# MCU_Standard.net
KiCad netlist of a schematic drawn in EAGLE
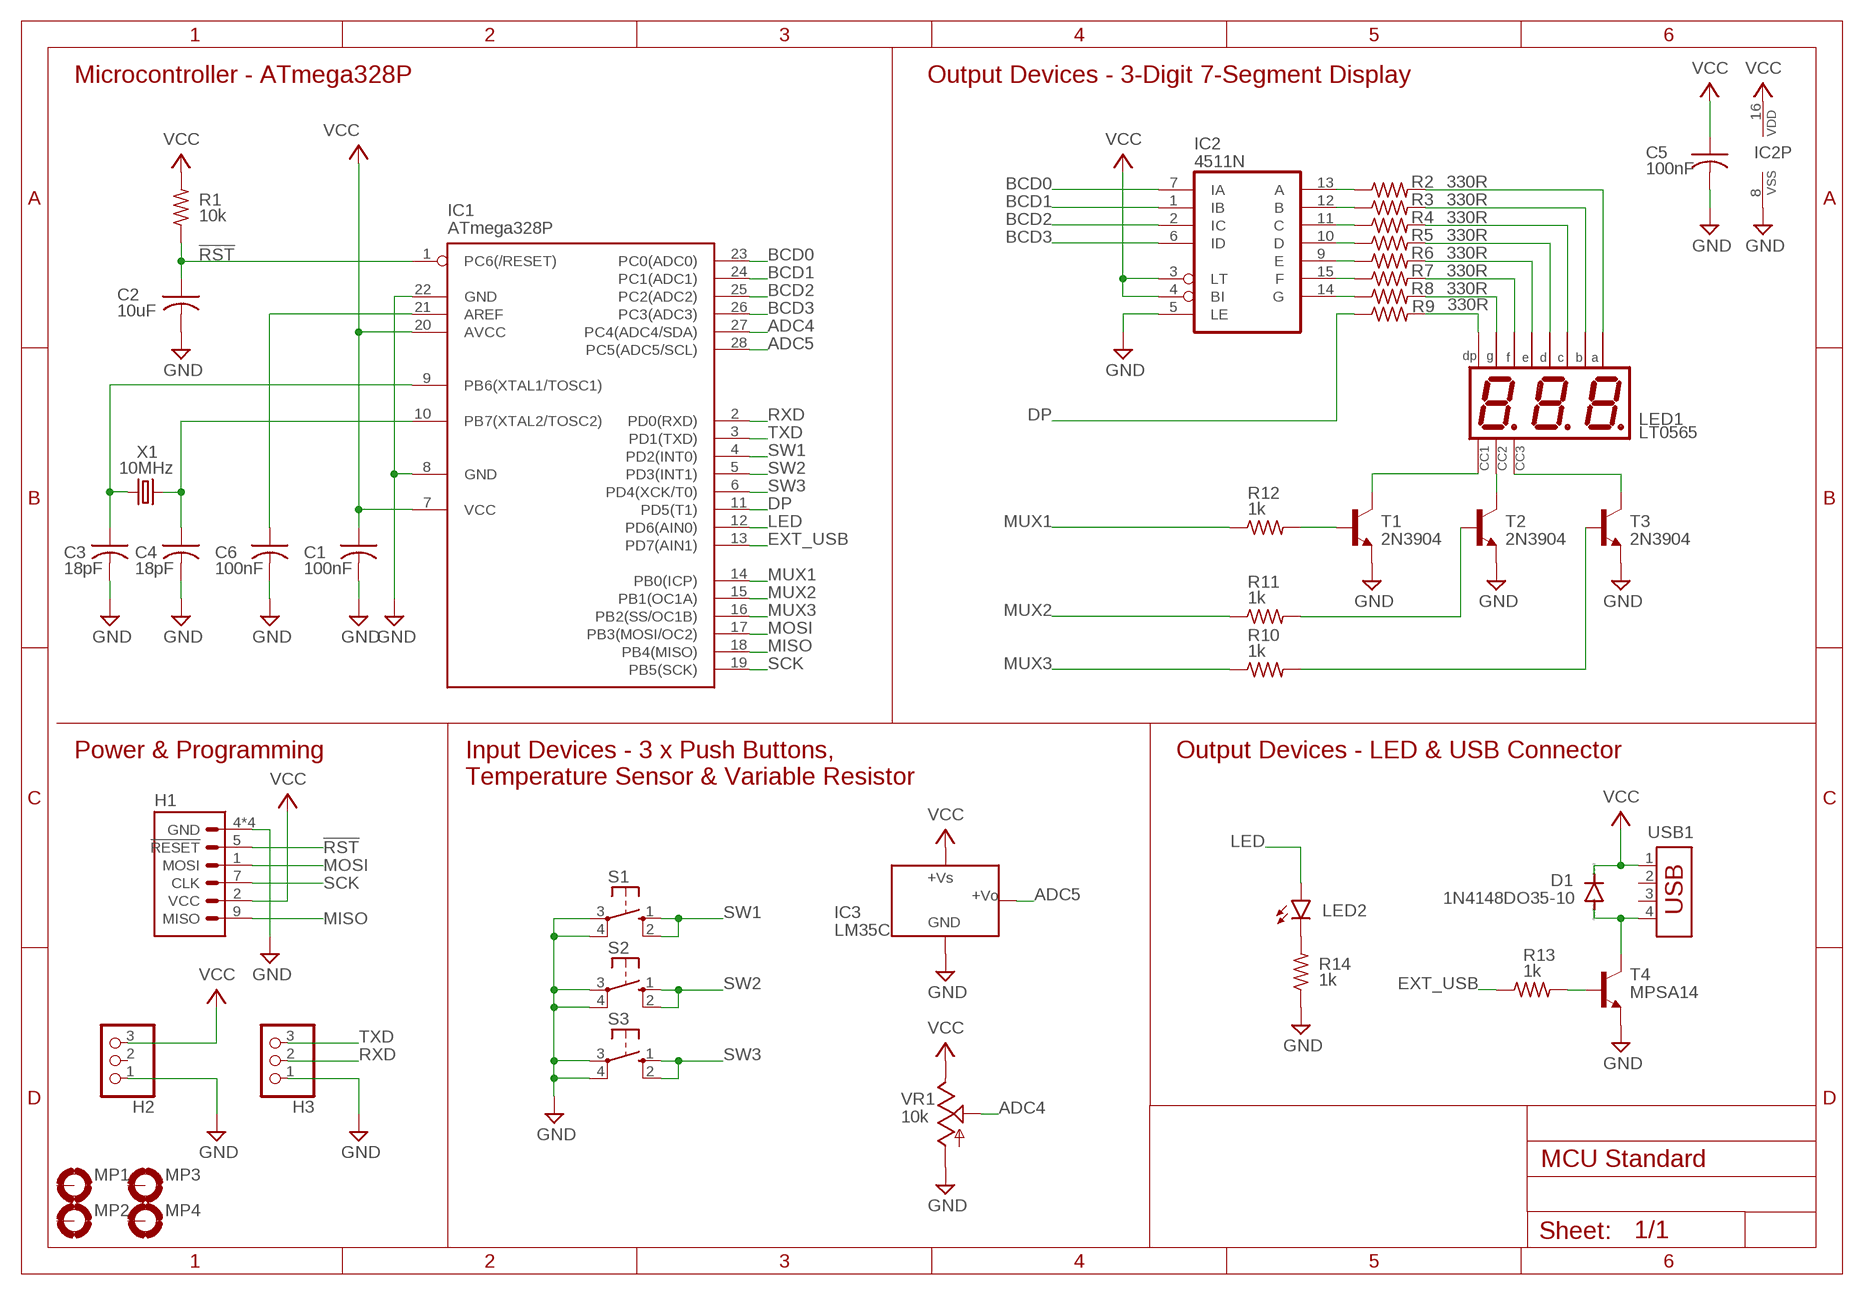
[diagram p0: schematic, sheet 1]

(export (version "E")
  (design (tool "Eeschema 10.0.6"))
  (components
    (comp (ref "C1")
      (value "100nF")
      (footprint "eagle-import:C050-024X044")
      (libsource (lib "eagle-import") (part "C-US050-024X044"))
    )
    (comp (ref "C2")
      (value "10uF")
      (footprint "eagle-import:C050-024X044")
      (libsource (lib "eagle-import") (part "C-US050-024X044"))
    )
    (comp (ref "C3")
      (value "18pF")
      (footprint "eagle-import:C050-024X044")
      (libsource (lib "eagle-import") (part "C-US050-024X044"))
    )
    (comp (ref "C4")
      (value "18pF")
      (footprint "eagle-import:C050-024X044")
      (libsource (lib "eagle-import") (part "C-US050-024X044"))
    )
    (comp (ref "C5")
      (value "100nF")
      (footprint "eagle-import:C050-024X044")
      (libsource (lib "eagle-import") (part "C-US050-024X044"))
    )
    (comp (ref "C6")
      (value "100nF")
      (footprint "eagle-import:C050-024X044")
      (libsource (lib "eagle-import") (part "C-US050-024X044"))
    )
    (comp (ref "D1")
      (value "1N4148DO35-10")
      (footprint "eagle-import:DO35-10")
      (libsource (lib "eagle-import") (part "1N4148DO35-10"))
    )
    (comp (ref "H1")
      (value "MISO_MOSI_IPC-10V")
      (footprint "eagle-import:IDC-10V")
      (libsource (lib "eagle-import") (part "MISO_MOSI_IPC-10V"))
    )
    (comp (ref "H2")
      (value "PINHD-1X03_2.54-90°")
      (footprint "eagle-import:1X03_90")
      (libsource (lib "eagle-import") (part "PINHD-1X03_2.54-90°"))
    )
    (comp (ref "H3")
      (value "PINHD-1X03_2.54-90°")
      (footprint "eagle-import:1X03_90")
      (libsource (lib "eagle-import") (part "PINHD-1X03_2.54-90°"))
    )
    (comp (ref "IC1")
      (value "ATmega328P")
      (footprint "eagle-import:DIL28-3")
      (libsource (lib "eagle-import") (part "MEGA8-P"))
    )
    (comp (ref "IC2")
      (value "4511N")
      (footprint "eagle-import:DIL16")
      (libsource (lib "eagle-import") (part "4511N"))
    )
    (comp (ref "IC3")
      (value "LM35C")
      (footprint "eagle-import:TO92")
      (libsource (lib "eagle-import") (part "LM35C"))
    )
    (comp (ref "LED1")
      (value "LT0565")
      (footprint "eagle-import:BX56_BX55")
      (libsource (lib "eagle-import") (part "LT0565"))
    )
    (comp (ref "LED2")
      (value "LED3MM")
      (footprint "eagle-import:LED3MM")
      (libsource (lib "eagle-import") (part "LED3MM"))
    )
    (comp (ref "MP1")
      (value "MOUNT-PAD-ROUND3.2")
      (footprint "eagle-import:3,2-PAD")
      (libsource (lib "eagle-import") (part "MOUNT-PAD-ROUND3.2"))
    )
    (comp (ref "MP2")
      (value "MOUNT-PAD-ROUND3.2")
      (footprint "eagle-import:3,2-PAD")
      (libsource (lib "eagle-import") (part "MOUNT-PAD-ROUND3.2"))
    )
    (comp (ref "MP3")
      (value "MOUNT-PAD-ROUND3.2")
      (footprint "eagle-import:3,2-PAD")
      (libsource (lib "eagle-import") (part "MOUNT-PAD-ROUND3.2"))
    )
    (comp (ref "MP4")
      (value "MOUNT-PAD-ROUND3.2")
      (footprint "eagle-import:3,2-PAD")
      (libsource (lib "eagle-import") (part "MOUNT-PAD-ROUND3.2"))
    )
    (comp (ref "R1")
      (value "10k")
      (footprint "eagle-import:0207_10")
      (libsource (lib "eagle-import") (part "R-US_0207/10"))
    )
    (comp (ref "R2")
      (value "330R")
      (footprint "eagle-import:0207_10")
      (libsource (lib "eagle-import") (part "R-US_0207/10"))
    )
    (comp (ref "R3")
      (value "330R")
      (footprint "eagle-import:0207_10")
      (libsource (lib "eagle-import") (part "R-US_0207/10"))
    )
    (comp (ref "R4")
      (value "330R")
      (footprint "eagle-import:0207_10")
      (libsource (lib "eagle-import") (part "R-US_0207/10"))
    )
    (comp (ref "R5")
      (value "330R")
      (footprint "eagle-import:0207_10")
      (libsource (lib "eagle-import") (part "R-US_0207/10"))
    )
    (comp (ref "R6")
      (value "330R")
      (footprint "eagle-import:0207_10")
      (libsource (lib "eagle-import") (part "R-US_0207/10"))
    )
    (comp (ref "R7")
      (value "330R")
      (footprint "eagle-import:0207_10")
      (libsource (lib "eagle-import") (part "R-US_0207/10"))
    )
    (comp (ref "R8")
      (value "330R")
      (footprint "eagle-import:0207_10")
      (libsource (lib "eagle-import") (part "R-US_0207/10"))
    )
    (comp (ref "R9")
      (value "330R")
      (footprint "eagle-import:0207_10")
      (libsource (lib "eagle-import") (part "R-US_0207/10"))
    )
    (comp (ref "R10")
      (value "1k")
      (footprint "eagle-import:0207_10")
      (libsource (lib "eagle-import") (part "R-US_0207/10"))
    )
    (comp (ref "R11")
      (value "1k")
      (footprint "eagle-import:0207_10")
      (libsource (lib "eagle-import") (part "R-US_0207/10"))
    )
    (comp (ref "R12")
      (value "1k")
      (footprint "eagle-import:0207_10")
      (libsource (lib "eagle-import") (part "R-US_0207/10"))
    )
    (comp (ref "R13")
      (value "1k")
      (footprint "eagle-import:0207_10")
      (libsource (lib "eagle-import") (part "R-US_0207/10"))
    )
    (comp (ref "R14")
      (value "1k")
      (footprint "eagle-import:0207_10")
      (libsource (lib "eagle-import") (part "R-US_0207/10"))
    )
    (comp (ref "S1")
      (value "10-XX")
      (footprint "eagle-import:B3F-10XX")
      (fields (field (name "MPN") "B3F-1000"))
      (libsource (lib "eagle-import") (part "10-XX"))
    )
    (comp (ref "S2")
      (value "10-XX")
      (footprint "eagle-import:B3F-10XX")
      (fields (field (name "MPN") "B3F-1000"))
      (libsource (lib "eagle-import") (part "10-XX"))
    )
    (comp (ref "S3")
      (value "10-XX")
      (footprint "eagle-import:B3F-10XX")
      (fields (field (name "MPN") "B3F-1000"))
      (libsource (lib "eagle-import") (part "10-XX"))
    )
    (comp (ref "T1")
      (value "2N3904")
      (footprint "eagle-import:TO92")
      (libsource (lib "eagle-import") (part "2N3904"))
    )
    (comp (ref "T2")
      (value "2N3904")
      (footprint "eagle-import:TO92")
      (libsource (lib "eagle-import") (part "2N3904"))
    )
    (comp (ref "T3")
      (value "2N3904")
      (footprint "eagle-import:TO92")
      (libsource (lib "eagle-import") (part "2N3904"))
    )
    (comp (ref "T4")
      (value "MPSA14")
      (footprint "eagle-import:TO92")
      (libsource (lib "eagle-import") (part "MPSA14"))
    )
    (comp (ref "USB1")
      (value "USB-787616")
      (footprint "eagle-import:USB")
      (libsource (lib "eagle-import") (part "USB-787616"))
    )
    (comp (ref "VR1")
      (value "10k")
      (footprint "eagle-import:PT-10")
      (libsource (lib "eagle-import") (part "POTENTIOMETER_PT10"))
    )
    (comp (ref "X1")
      (value "10MHz")
      (footprint "eagle-import:HC49_S")
      (libsource (lib "eagle-import") (part "CRYSTAL_HC49/S"))
    )
  )
  (nets
    (net (code "1") (name "/ADC4") (class "Default")
      (node (ref "IC1") (pin "27") (pinfunction "PC4(ADC4/SDA)_27") (pintype "bidirectional"))
      (node (ref "VR1") (pin "3") (pinfunction "S_3") (pintype "passive"))
    )
    (net (code "2") (name "/ADC5") (class "Default")
      (node (ref "IC1") (pin "28") (pinfunction "PC5(ADC5/SCL)_28") (pintype "bidirectional"))
      (node (ref "IC3") (pin "2") (pinfunction "VO_2") (pintype "output"))
    )
    (net (code "3") (name "/BCD0") (class "Default")
      (node (ref "IC1") (pin "23") (pinfunction "PC0(ADC0)_23") (pintype "bidirectional"))
      (node (ref "IC2") (pin "7") (pinfunction "IA_7") (pintype "input"))
    )
    (net (code "4") (name "/BCD1") (class "Default")
      (node (ref "IC1") (pin "24") (pinfunction "PC1(ADC1)_24") (pintype "bidirectional"))
      (node (ref "IC2") (pin "1") (pinfunction "IB_1") (pintype "input"))
    )
    (net (code "5") (name "/BCD2") (class "Default")
      (node (ref "IC1") (pin "25") (pinfunction "PC2(ADC2)_25") (pintype "bidirectional"))
      (node (ref "IC2") (pin "2") (pinfunction "IC_2") (pintype "input"))
    )
    (net (code "6") (name "/BCD3") (class "Default")
      (node (ref "IC1") (pin "26") (pinfunction "PC3(ADC3)_26") (pintype "bidirectional"))
      (node (ref "IC2") (pin "6") (pinfunction "ID_6") (pintype "input"))
    )
    (net (code "7") (name "/DP") (class "Default")
      (node (ref "IC1") (pin "11") (pinfunction "PD5(T1)_11") (pintype "bidirectional"))
      (node (ref "R9") (pin "1") (pinfunction "1_1") (pintype "passive"))
    )
    (net (code "8") (name "/EXT_USB") (class "Default")
      (node (ref "IC1") (pin "13") (pinfunction "PD7(AIN1)_13") (pintype "bidirectional"))
      (node (ref "R13") (pin "1") (pinfunction "1_1") (pintype "passive"))
    )
    (net (code "9") (name "/LED") (class "Default")
      (node (ref "IC1") (pin "12") (pinfunction "PD6(AIN0)_12") (pintype "bidirectional"))
      (node (ref "LED2") (pin "A") (pinfunction "A_A") (pintype "passive"))
    )
    (net (code "10") (name "/MISO") (class "Default")
      (node (ref "H1") (pin "9") (pinfunction "MISO_9") (pintype "passive"))
      (node (ref "IC1") (pin "18") (pinfunction "PB4(MISO)_18") (pintype "bidirectional"))
    )
    (net (code "11") (name "/MOSI") (class "Default")
      (node (ref "H1") (pin "1") (pinfunction "MOSI_1") (pintype "passive"))
      (node (ref "IC1") (pin "17") (pinfunction "PB3(MOSI/OC2)_17") (pintype "bidirectional"))
    )
    (net (code "12") (name "/MUX1") (class "Default")
      (node (ref "IC1") (pin "14") (pinfunction "PB0(ICP)_14") (pintype "bidirectional"))
      (node (ref "R12") (pin "1") (pinfunction "1_1") (pintype "passive"))
    )
    (net (code "13") (name "/MUX2") (class "Default")
      (node (ref "IC1") (pin "15") (pinfunction "PB1(OC1A)_15") (pintype "bidirectional"))
      (node (ref "R11") (pin "1") (pinfunction "1_1") (pintype "passive"))
    )
    (net (code "14") (name "/MUX3") (class "Default")
      (node (ref "IC1") (pin "16") (pinfunction "PB2(SS/OC1B)_16") (pintype "bidirectional"))
      (node (ref "R10") (pin "1") (pinfunction "1_1") (pintype "passive"))
    )
    (net (code "15") (name "/RXD") (class "Default")
      (node (ref "H3") (pin "2") (pinfunction "2_2") (pintype "passive"))
      (node (ref "IC1") (pin "2") (pinfunction "PD0(RXD)_2") (pintype "bidirectional"))
    )
    (net (code "16") (name "/SCK") (class "Default")
      (node (ref "H1") (pin "7") (pinfunction "CLK_7") (pintype "passive"))
      (node (ref "IC1") (pin "19") (pinfunction "PB5(SCK)_19") (pintype "bidirectional"))
    )
    (net (code "17") (name "/SW1") (class "Default")
      (node (ref "IC1") (pin "4") (pinfunction "PD2(INT0)_4") (pintype "bidirectional"))
      (node (ref "S1") (pin "1") (pinfunction "S_1") (pintype "passive"))
      (node (ref "S1") (pin "2") (pinfunction "S1_2") (pintype "passive"))
    )
    (net (code "18") (name "/SW2") (class "Default")
      (node (ref "IC1") (pin "5") (pinfunction "PD3(INT1)_5") (pintype "bidirectional"))
      (node (ref "S2") (pin "1") (pinfunction "S_1") (pintype "passive"))
      (node (ref "S2") (pin "2") (pinfunction "S1_2") (pintype "passive"))
    )
    (net (code "19") (name "/SW3") (class "Default")
      (node (ref "IC1") (pin "6") (pinfunction "PD4(XCK/T0)_6") (pintype "bidirectional"))
      (node (ref "S3") (pin "1") (pinfunction "S_1") (pintype "passive"))
      (node (ref "S3") (pin "2") (pinfunction "S1_2") (pintype "passive"))
    )
    (net (code "20") (name "/TXD") (class "Default")
      (node (ref "H3") (pin "3") (pinfunction "3_3") (pintype "passive"))
      (node (ref "IC1") (pin "3") (pinfunction "PD1(TXD)_3") (pintype "bidirectional"))
    )
    (net (code "21") (name "/~{RST}") (class "Default")
      (node (ref "C2") (pin "1") (pinfunction "1_1") (pintype "passive"))
      (node (ref "H1") (pin "5") (pinfunction "~{RESET}_5") (pintype "passive"))
      (node (ref "IC1") (pin "1") (pinfunction "PC6(/RESET)_1") (pintype "bidirectional"))
      (node (ref "R1") (pin "1") (pinfunction "1_1") (pintype "passive"))
    )
    (net (code "22") (name "GND") (class "Default")
      (node (ref "C1") (pin "2") (pinfunction "2_2") (pintype "passive"))
      (node (ref "C2") (pin "2") (pinfunction "2_2") (pintype "passive"))
      (node (ref "C3") (pin "2") (pinfunction "2_2") (pintype "passive"))
      (node (ref "C4") (pin "2") (pinfunction "2_2") (pintype "passive"))
      (node (ref "C5") (pin "2") (pinfunction "2_2") (pintype "passive"))
      (node (ref "C6") (pin "2") (pinfunction "2_2") (pintype "passive"))
      (node (ref "H1") (pin "10") (pinfunction "GND_10") (pintype "power_in"))
      (node (ref "H1") (pin "4") (pinfunction "GND_4") (pintype "power_in"))
      (node (ref "H1") (pin "6") (pinfunction "GND_6") (pintype "power_in"))
      (node (ref "H1") (pin "8") (pinfunction "GND_8") (pintype "power_in"))
      (node (ref "H2") (pin "1") (pinfunction "1_1") (pintype "passive"))
      (node (ref "H3") (pin "1") (pinfunction "1_1") (pintype "passive"))
      (node (ref "IC1") (pin "22") (pinfunction "GND_22") (pintype "power_in"))
      (node (ref "IC1") (pin "8") (pinfunction "GND_8") (pintype "power_in"))
      (node (ref "IC2") (pin "5") (pinfunction "LE_5") (pintype "input"))
      (node (ref "IC2") (pin "8") (pinfunction "VSS_8") (pintype "power_in"))
      (node (ref "IC3") (pin "1") (pinfunction "GND_1") (pintype "power_in"))
      (node (ref "R14") (pin "1") (pinfunction "1_1") (pintype "passive"))
      (node (ref "S1") (pin "3") (pinfunction "P_3") (pintype "passive"))
      (node (ref "S1") (pin "4") (pinfunction "P1_4") (pintype "passive"))
      (node (ref "S2") (pin "3") (pinfunction "P_3") (pintype "passive"))
      (node (ref "S2") (pin "4") (pinfunction "P1_4") (pintype "passive"))
      (node (ref "S3") (pin "3") (pinfunction "P_3") (pintype "passive"))
      (node (ref "S3") (pin "4") (pinfunction "P1_4") (pintype "passive"))
      (node (ref "T1") (pin "3") (pinfunction "E_3") (pintype "passive"))
      (node (ref "T2") (pin "3") (pinfunction "E_3") (pintype "passive"))
      (node (ref "T3") (pin "3") (pinfunction "E_3") (pintype "passive"))
      (node (ref "T4") (pin "3") (pinfunction "E_3") (pintype "passive"))
      (node (ref "VR1") (pin "1") (pinfunction "A_1") (pintype "passive"))
    )
    (net (code "23") (name "Net-(IC1-AREF)") (class "Default")
      (node (ref "C6") (pin "1") (pinfunction "1_1") (pintype "passive"))
      (node (ref "IC1") (pin "21") (pinfunction "AREF_21") (pintype "passive"))
    )
    (net (code "24") (name "Net-(IC1-PB6(XTAL1{slash}TOSC1))") (class "Default")
      (node (ref "C3") (pin "1") (pinfunction "1_1") (pintype "passive"))
      (node (ref "IC1") (pin "9") (pinfunction "PB6(XTAL1/TOSC1)_9") (pintype "bidirectional"))
      (node (ref "X1") (pin "1") (pinfunction "1_1") (pintype "passive"))
    )
    (net (code "25") (name "Net-(IC1-PB7(XTAL2{slash}TOSC2))") (class "Default")
      (node (ref "C4") (pin "1") (pinfunction "1_1") (pintype "passive"))
      (node (ref "IC1") (pin "10") (pinfunction "PB7(XTAL2/TOSC2)_10") (pintype "bidirectional"))
      (node (ref "X1") (pin "2") (pinfunction "2_2") (pintype "passive"))
    )
    (net (code "26") (name "Net-(IC2A-A)") (class "Default")
      (node (ref "IC2") (pin "13") (pinfunction "A_13") (pintype "output"))
      (node (ref "R2") (pin "1") (pinfunction "1_1") (pintype "passive"))
    )
    (net (code "27") (name "Net-(IC2A-B)") (class "Default")
      (node (ref "IC2") (pin "12") (pinfunction "B_12") (pintype "output"))
      (node (ref "R3") (pin "1") (pinfunction "1_1") (pintype "passive"))
    )
    (net (code "28") (name "Net-(IC2A-C)") (class "Default")
      (node (ref "IC2") (pin "11") (pinfunction "C_11") (pintype "output"))
      (node (ref "R4") (pin "1") (pinfunction "1_1") (pintype "passive"))
    )
    (net (code "29") (name "Net-(IC2A-D)") (class "Default")
      (node (ref "IC2") (pin "10") (pinfunction "D_10") (pintype "output"))
      (node (ref "R5") (pin "1") (pinfunction "1_1") (pintype "passive"))
    )
    (net (code "30") (name "Net-(IC2A-E)") (class "Default")
      (node (ref "IC2") (pin "9") (pinfunction "E_9") (pintype "output"))
      (node (ref "R6") (pin "1") (pinfunction "1_1") (pintype "passive"))
    )
    (net (code "31") (name "Net-(IC2A-F)") (class "Default")
      (node (ref "IC2") (pin "15") (pinfunction "F_15") (pintype "output"))
      (node (ref "R7") (pin "1") (pinfunction "1_1") (pintype "passive"))
    )
    (net (code "32") (name "Net-(IC2A-G)") (class "Default")
      (node (ref "IC2") (pin "14") (pinfunction "G_14") (pintype "output"))
      (node (ref "R8") (pin "1") (pinfunction "1_1") (pintype "passive"))
    )
    (net (code "33") (name "Net-(LED1-A)") (class "Default")
      (node (ref "LED1") (pin "11") (pinfunction "A_11") (pintype "passive"))
      (node (ref "R2") (pin "2") (pinfunction "2_2") (pintype "passive"))
    )
    (net (code "34") (name "Net-(LED1-B)") (class "Default")
      (node (ref "LED1") (pin "7") (pinfunction "B_7") (pintype "passive"))
      (node (ref "R3") (pin "2") (pinfunction "2_2") (pintype "passive"))
    )
    (net (code "35") (name "Net-(LED1-C)") (class "Default")
      (node (ref "LED1") (pin "4") (pinfunction "C_4") (pintype "passive"))
      (node (ref "R4") (pin "2") (pinfunction "2_2") (pintype "passive"))
    )
    (net (code "36") (name "Net-(LED1-D)") (class "Default")
      (node (ref "LED1") (pin "2") (pinfunction "D_2") (pintype "passive"))
      (node (ref "R5") (pin "2") (pinfunction "2_2") (pintype "passive"))
    )
    (net (code "37") (name "Net-(LED1-DP)") (class "Default")
      (node (ref "LED1") (pin "3") (pinfunction "DP_3") (pintype "passive"))
      (node (ref "R9") (pin "2") (pinfunction "2_2") (pintype "passive"))
    )
    (net (code "38") (name "Net-(LED1-E)") (class "Default")
      (node (ref "LED1") (pin "1") (pinfunction "E_1") (pintype "passive"))
      (node (ref "R6") (pin "2") (pinfunction "2_2") (pintype "passive"))
    )
    (net (code "39") (name "Net-(LED1-F)") (class "Default")
      (node (ref "LED1") (pin "10") (pinfunction "F_10") (pintype "passive"))
      (node (ref "R7") (pin "2") (pinfunction "2_2") (pintype "passive"))
    )
    (net (code "40") (name "Net-(LED1-G)") (class "Default")
      (node (ref "LED1") (pin "5") (pinfunction "G_5") (pintype "passive"))
      (node (ref "R8") (pin "2") (pinfunction "2_2") (pintype "passive"))
    )
    (net (code "41") (name "Net-(LED2-C)") (class "Default")
      (node (ref "LED2") (pin "K") (pinfunction "C_K") (pintype "passive"))
      (node (ref "R14") (pin "2") (pinfunction "2_2") (pintype "passive"))
    )
    (net (code "42") (name "Net-(T1-B)") (class "Default")
      (node (ref "R12") (pin "2") (pinfunction "2_2") (pintype "passive"))
      (node (ref "T1") (pin "2") (pinfunction "B_2") (pintype "passive"))
    )
    (net (code "43") (name "Net-(T1-C)") (class "Default")
      (node (ref "LED1") (pin "12") (pinfunction "CA_12") (pintype "passive"))
      (node (ref "T1") (pin "1") (pinfunction "C_1") (pintype "passive"))
    )
    (net (code "44") (name "Net-(T2-B)") (class "Default")
      (node (ref "R11") (pin "2") (pinfunction "2_2") (pintype "passive"))
      (node (ref "T2") (pin "2") (pinfunction "B_2") (pintype "passive"))
    )
    (net (code "45") (name "Net-(T2-C)") (class "Default")
      (node (ref "LED1") (pin "9") (pinfunction "CA_9") (pintype "passive"))
      (node (ref "T2") (pin "1") (pinfunction "C_1") (pintype "passive"))
    )
    (net (code "46") (name "Net-(T3-B)") (class "Default")
      (node (ref "R10") (pin "2") (pinfunction "2_2") (pintype "passive"))
      (node (ref "T3") (pin "2") (pinfunction "B_2") (pintype "passive"))
    )
    (net (code "47") (name "Net-(T3-C)") (class "Default")
      (node (ref "LED1") (pin "8") (pinfunction "CA_8") (pintype "passive"))
      (node (ref "T3") (pin "1") (pinfunction "C_1") (pintype "passive"))
    )
    (net (code "48") (name "Net-(T4-B)") (class "Default")
      (node (ref "R13") (pin "2") (pinfunction "2_2") (pintype "passive"))
      (node (ref "T4") (pin "2") (pinfunction "B_2") (pintype "passive"))
    )
    (net (code "49") (name "Net-(T4-C)") (class "Default")
      (node (ref "D1") (pin "A") (pinfunction "A_A") (pintype "passive"))
      (node (ref "T4") (pin "1") (pinfunction "C_1") (pintype "passive"))
      (node (ref "USB1") (pin "4") (pinfunction "4_4") (pintype "passive"))
    )
    (net (code "50") (name "VCC") (class "Default")
      (node (ref "C1") (pin "1") (pinfunction "1_1") (pintype "passive"))
      (node (ref "C5") (pin "1") (pinfunction "1_1") (pintype "passive"))
      (node (ref "D1") (pin "C") (pinfunction "C_C") (pintype "passive"))
      (node (ref "H1") (pin "2") (pinfunction "VCC_2") (pintype "power_in"))
      (node (ref "H2") (pin "3") (pinfunction "3_3") (pintype "passive"))
      (node (ref "IC1") (pin "20") (pinfunction "AVCC_20") (pintype "power_in"))
      (node (ref "IC1") (pin "7") (pinfunction "VCC_7") (pintype "power_in"))
      (node (ref "IC2") (pin "16") (pinfunction "VDD_16") (pintype "power_in"))
      (node (ref "IC2") (pin "3") (pinfunction "LT_3") (pintype "input"))
      (node (ref "IC2") (pin "4") (pinfunction "BI_4") (pintype "input"))
      (node (ref "IC3") (pin "3") (pinfunction "+VS_3") (pintype "power_in"))
      (node (ref "R1") (pin "2") (pinfunction "2_2") (pintype "passive"))
      (node (ref "USB1") (pin "1") (pinfunction "1_1") (pintype "passive"))
      (node (ref "VR1") (pin "2") (pinfunction "E_2") (pintype "passive"))
    )
    (net (code "51") (name "unconnected-(H2-Pad2)") (class "Default")
      (node (ref "H2") (pin "2") (pinfunction "2_2") (pintype "passive"))
    )
    (net (code "52") (name "unconnected-(MP1-MOUNT-PadB3,2)") (class "Default")
      (node (ref "MP1") (pin "B3,2") (pinfunction "MOUNT_B3,2") (pintype "passive"))
    )
    (net (code "53") (name "unconnected-(MP2-MOUNT-PadB3,2)") (class "Default")
      (node (ref "MP2") (pin "B3,2") (pinfunction "MOUNT_B3,2") (pintype "passive"))
    )
    (net (code "54") (name "unconnected-(MP3-MOUNT-PadB3,2)") (class "Default")
      (node (ref "MP3") (pin "B3,2") (pinfunction "MOUNT_B3,2") (pintype "passive"))
    )
    (net (code "55") (name "unconnected-(MP4-MOUNT-PadB3,2)") (class "Default")
      (node (ref "MP4") (pin "B3,2") (pinfunction "MOUNT_B3,2") (pintype "passive"))
    )
    (net (code "56") (name "unconnected-(USB1-Pad2)") (class "Default")
      (node (ref "USB1") (pin "2") (pinfunction "2_2") (pintype "passive"))
    )
    (net (code "57") (name "unconnected-(USB1-Pad3)") (class "Default")
      (node (ref "USB1") (pin "3") (pinfunction "3_3") (pintype "passive"))
    )
  )
)
